# 14_FEP.net
KiCad netlist of a schematic drawn in Altium Designer
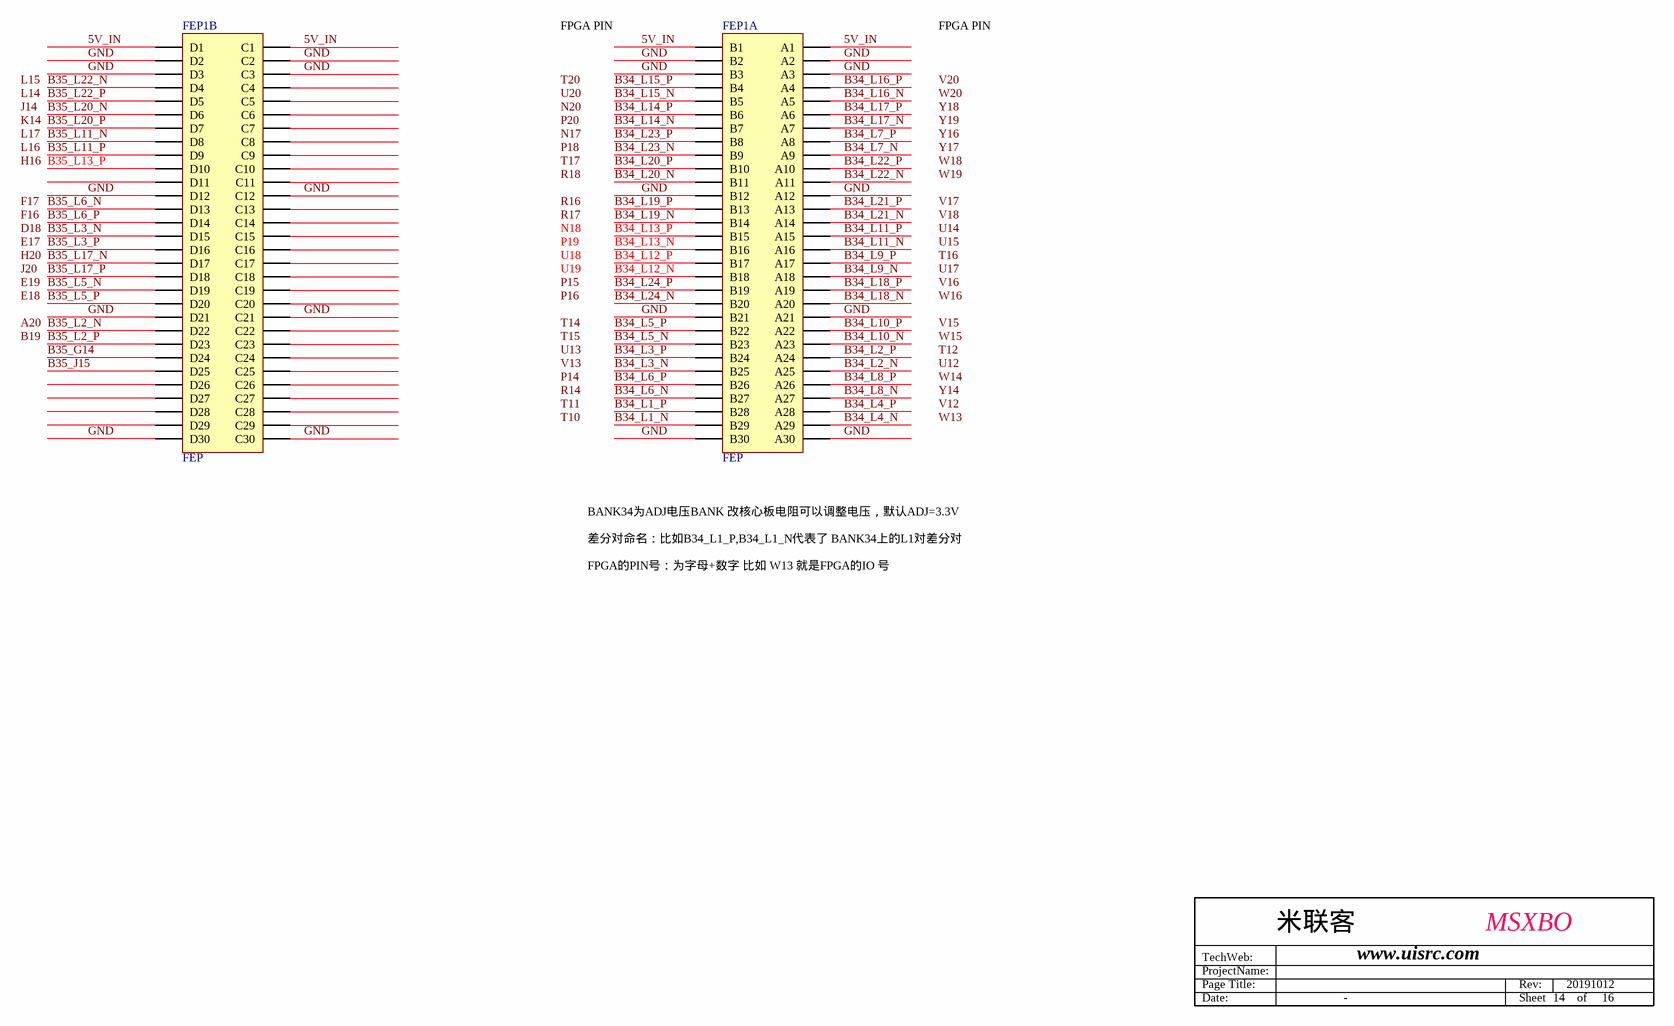
[diagram p0: 14_FEP.SchDoc]

(export (version "E")
  (design (tool "Eeschema 10.0.6"))
  (components
    (comp (ref "FEP1") (value "FEP") (footprint "FEP-X2") (libsource (lib "MIZ7035_Fun") (part "FEP-2X")))
  )
  (nets
    (net (code "1") (name "/5V_IN") (class "Default")
      (node (ref "FEP1") (pin "A1") (pinfunction "A1_A1") (pintype "passive"))
      (node (ref "FEP1") (pin "B1") (pinfunction "B1_B1") (pintype "passive"))
      (node (ref "FEP1") (pin "C1") (pinfunction "C1_C1") (pintype "passive"))
      (node (ref "FEP1") (pin "D1") (pinfunction "D1_D1") (pintype "passive"))
    )
    (net (code "4") (name "/B34_L1_N") (class "Default")
      (node (ref "FEP1") (pin "B29") (pinfunction "B29_B29") (pintype "passive"))
    )
    (net (code "5") (name "/B34_L1_P") (class "Default")
      (node (ref "FEP1") (pin "B28") (pinfunction "B28_B28") (pintype "passive"))
    )
    (net (code "6") (name "/B34_L2_N") (class "Default")
      (node (ref "FEP1") (pin "A25") (pinfunction "A25_A25") (pintype "passive"))
    )
    (net (code "7") (name "/B34_L2_P") (class "Default")
      (node (ref "FEP1") (pin "A24") (pinfunction "A24_A24") (pintype "passive"))
    )
    (net (code "8") (name "/B34_L3_N") (class "Default")
      (node (ref "FEP1") (pin "B25") (pinfunction "B25_B25") (pintype "passive"))
    )
    (net (code "9") (name "/B34_L3_P") (class "Default")
      (node (ref "FEP1") (pin "B24") (pinfunction "B24_B24") (pintype "passive"))
    )
    (net (code "10") (name "/B34_L4_N") (class "Default")
      (node (ref "FEP1") (pin "A29") (pinfunction "A29_A29") (pintype "passive"))
    )
    (net (code "11") (name "/B34_L4_P") (class "Default")
      (node (ref "FEP1") (pin "A28") (pinfunction "A28_A28") (pintype "passive"))
    )
    (net (code "12") (name "/B34_L5_N") (class "Default")
      (node (ref "FEP1") (pin "B23") (pinfunction "B23_B23") (pintype "passive"))
    )
    (net (code "13") (name "/B34_L5_P") (class "Default")
      (node (ref "FEP1") (pin "B22") (pinfunction "B22_B22") (pintype "passive"))
    )
    (net (code "14") (name "/B34_L6_N") (class "Default")
      (node (ref "FEP1") (pin "B27") (pinfunction "B27_B27") (pintype "passive"))
    )
    (net (code "15") (name "/B34_L6_P") (class "Default")
      (node (ref "FEP1") (pin "B26") (pinfunction "B26_B26") (pintype "passive"))
    )
    (net (code "16") (name "/B34_L7_N") (class "Default")
      (node (ref "FEP1") (pin "A9") (pinfunction "A9_A9") (pintype "passive"))
    )
    (net (code "17") (name "/B34_L7_P") (class "Default")
      (node (ref "FEP1") (pin "A8") (pinfunction "A8_A8") (pintype "passive"))
    )
    (net (code "18") (name "/B34_L8_N") (class "Default")
      (node (ref "FEP1") (pin "A27") (pinfunction "A27_A27") (pintype "passive"))
    )
    (net (code "19") (name "/B34_L8_P") (class "Default")
      (node (ref "FEP1") (pin "A26") (pinfunction "A26_A26") (pintype "passive"))
    )
    (net (code "20") (name "/B34_L9_N") (class "Default")
      (node (ref "FEP1") (pin "A18") (pinfunction "A18_A18") (pintype "passive"))
    )
    (net (code "21") (name "/B34_L9_P") (class "Default")
      (node (ref "FEP1") (pin "A17") (pinfunction "A17_A17") (pintype "passive"))
    )
    (net (code "22") (name "/B34_L10_N") (class "Default")
      (node (ref "FEP1") (pin "A23") (pinfunction "A23_A23") (pintype "passive"))
    )
    (net (code "23") (name "/B34_L10_P") (class "Default")
      (node (ref "FEP1") (pin "A22") (pinfunction "A22_A22") (pintype "passive"))
    )
    (net (code "24") (name "/B34_L11_N") (class "Default")
      (node (ref "FEP1") (pin "A16") (pinfunction "A16_A16") (pintype "passive"))
    )
    (net (code "25") (name "/B34_L11_P") (class "Default")
      (node (ref "FEP1") (pin "A15") (pinfunction "A15_A15") (pintype "passive"))
    )
    (net (code "26") (name "/B34_L12_N") (class "Default")
      (node (ref "FEP1") (pin "B18") (pinfunction "B18_B18") (pintype "passive"))
    )
    (net (code "27") (name "/B34_L12_P") (class "Default")
      (node (ref "FEP1") (pin "B17") (pinfunction "B17_B17") (pintype "passive"))
    )
    (net (code "28") (name "/B34_L13_N") (class "Default")
      (node (ref "FEP1") (pin "B16") (pinfunction "B16_B16") (pintype "passive"))
    )
    (net (code "29") (name "/B34_L13_P") (class "Default")
      (node (ref "FEP1") (pin "B15") (pinfunction "B15_B15") (pintype "passive"))
    )
    (net (code "30") (name "/B34_L14_N") (class "Default")
      (node (ref "FEP1") (pin "B7") (pinfunction "B7_B7") (pintype "passive"))
    )
    (net (code "31") (name "/B34_L14_P") (class "Default")
      (node (ref "FEP1") (pin "B6") (pinfunction "B6_B6") (pintype "passive"))
    )
    (net (code "32") (name "/B34_L15_N") (class "Default")
      (node (ref "FEP1") (pin "B5") (pinfunction "B5_B5") (pintype "passive"))
    )
    (net (code "33") (name "/B34_L15_P") (class "Default")
      (node (ref "FEP1") (pin "B4") (pinfunction "B4_B4") (pintype "passive"))
    )
    (net (code "34") (name "/B34_L16_N") (class "Default")
      (node (ref "FEP1") (pin "A5") (pinfunction "A5_A5") (pintype "passive"))
    )
    (net (code "35") (name "/B34_L16_P") (class "Default")
      (node (ref "FEP1") (pin "A4") (pinfunction "A4_A4") (pintype "passive"))
    )
    (net (code "36") (name "/B34_L17_N") (class "Default")
      (node (ref "FEP1") (pin "A7") (pinfunction "A7_A7") (pintype "passive"))
    )
    (net (code "37") (name "/B34_L17_P") (class "Default")
      (node (ref "FEP1") (pin "A6") (pinfunction "A6_A6") (pintype "passive"))
    )
    (net (code "38") (name "/B34_L18_N") (class "Default")
      (node (ref "FEP1") (pin "A20") (pinfunction "A20_A20") (pintype "passive"))
    )
    (net (code "39") (name "/B34_L18_P") (class "Default")
      (node (ref "FEP1") (pin "A19") (pinfunction "A19_A19") (pintype "passive"))
    )
    (net (code "40") (name "/B34_L19_N") (class "Default")
      (node (ref "FEP1") (pin "B14") (pinfunction "B14_B14") (pintype "passive"))
    )
    (net (code "41") (name "/B34_L19_P") (class "Default")
      (node (ref "FEP1") (pin "B13") (pinfunction "B13_B13") (pintype "passive"))
    )
    (net (code "42") (name "/B34_L20_N") (class "Default")
      (node (ref "FEP1") (pin "B11") (pinfunction "B11_B11") (pintype "passive"))
    )
    (net (code "43") (name "/B34_L20_P") (class "Default")
      (node (ref "FEP1") (pin "B10") (pinfunction "B10_B10") (pintype "passive"))
    )
    (net (code "44") (name "/B34_L21_N") (class "Default")
      (node (ref "FEP1") (pin "A14") (pinfunction "A14_A14") (pintype "passive"))
    )
    (net (code "45") (name "/B34_L21_P") (class "Default")
      (node (ref "FEP1") (pin "A13") (pinfunction "A13_A13") (pintype "passive"))
    )
    (net (code "46") (name "/B34_L22_N") (class "Default")
      (node (ref "FEP1") (pin "A11") (pinfunction "A11_A11") (pintype "passive"))
    )
    (net (code "47") (name "/B34_L22_P") (class "Default")
      (node (ref "FEP1") (pin "A10") (pinfunction "A10_A10") (pintype "passive"))
    )
    (net (code "48") (name "/B34_L23_N") (class "Default")
      (node (ref "FEP1") (pin "B9") (pinfunction "B9_B9") (pintype "passive"))
    )
    (net (code "49") (name "/B34_L23_P") (class "Default")
      (node (ref "FEP1") (pin "B8") (pinfunction "B8_B8") (pintype "passive"))
    )
    (net (code "50") (name "/B34_L24_N") (class "Default")
      (node (ref "FEP1") (pin "B20") (pinfunction "B20_B20") (pintype "passive"))
    )
    (net (code "51") (name "/B34_L24_P") (class "Default")
      (node (ref "FEP1") (pin "B19") (pinfunction "B19_B19") (pintype "passive"))
    )
    (net (code "52") (name "/B35_G14") (class "Default")
      (node (ref "FEP1") (pin "D24") (pinfunction "D24_D24") (pintype "passive"))
    )
    (net (code "53") (name "/B35_J15") (class "Default")
      (node (ref "FEP1") (pin "D25") (pinfunction "D25_D25") (pintype "passive"))
    )
    (net (code "54") (name "/B35_L2_N") (class "Default")
      (node (ref "FEP1") (pin "D22") (pinfunction "D22_D22") (pintype "passive"))
    )
    (net (code "55") (name "/B35_L2_P") (class "Default")
      (node (ref "FEP1") (pin "D23") (pinfunction "D23_D23") (pintype "passive"))
    )
    (net (code "56") (name "/B35_L3_N") (class "Default")
      (node (ref "FEP1") (pin "D15") (pinfunction "D15_D15") (pintype "passive"))
    )
    (net (code "57") (name "/B35_L3_P") (class "Default")
      (node (ref "FEP1") (pin "D16") (pinfunction "D16_D16") (pintype "passive"))
    )
    (net (code "58") (name "/B35_L5_N") (class "Default")
      (node (ref "FEP1") (pin "D19") (pinfunction "D19_D19") (pintype "passive"))
    )
    (net (code "59") (name "/B35_L5_P") (class "Default")
      (node (ref "FEP1") (pin "D20") (pinfunction "D20_D20") (pintype "passive"))
    )
    (net (code "60") (name "/B35_L6_N") (class "Default")
      (node (ref "FEP1") (pin "D13") (pinfunction "D13_D13") (pintype "passive"))
    )
    (net (code "61") (name "/B35_L6_P") (class "Default")
      (node (ref "FEP1") (pin "D14") (pinfunction "D14_D14") (pintype "passive"))
    )
    (net (code "62") (name "/B35_L11_N") (class "Default")
      (node (ref "FEP1") (pin "D8") (pinfunction "D8_D8") (pintype "passive"))
    )
    (net (code "63") (name "/B35_L11_P") (class "Default")
      (node (ref "FEP1") (pin "D9") (pinfunction "D9_D9") (pintype "passive"))
    )
    (net (code "64") (name "/B35_L13_P") (class "Default")
      (node (ref "FEP1") (pin "D10") (pinfunction "D10_D10") (pintype "passive"))
    )
    (net (code "65") (name "/B35_L17_N") (class "Default")
      (node (ref "FEP1") (pin "D17") (pinfunction "D17_D17") (pintype "passive"))
    )
    (net (code "66") (name "/B35_L17_P") (class "Default")
      (node (ref "FEP1") (pin "D18") (pinfunction "D18_D18") (pintype "passive"))
    )
    (net (code "67") (name "/B35_L20_N") (class "Default")
      (node (ref "FEP1") (pin "D6") (pinfunction "D6_D6") (pintype "passive"))
    )
    (net (code "68") (name "/B35_L20_P") (class "Default")
      (node (ref "FEP1") (pin "D7") (pinfunction "D7_D7") (pintype "passive"))
    )
    (net (code "69") (name "/B35_L22_N") (class "Default")
      (node (ref "FEP1") (pin "D4") (pinfunction "D4_D4") (pintype "passive"))
    )
    (net (code "70") (name "/B35_L22_P") (class "Default")
      (node (ref "FEP1") (pin "D5") (pinfunction "D5_D5") (pintype "passive"))
    )
    (net (code "77") (name "/GND") (class "Default")
      (node (ref "FEP1") (pin "A12") (pinfunction "A12_A12") (pintype "passive"))
      (node (ref "FEP1") (pin "A2") (pinfunction "A2_A2") (pintype "passive"))
      (node (ref "FEP1") (pin "A21") (pinfunction "A21_A21") (pintype "passive"))
      (node (ref "FEP1") (pin "A3") (pinfunction "A3_A3") (pintype "passive"))
      (node (ref "FEP1") (pin "A30") (pinfunction "A30_A30") (pintype "passive"))
      (node (ref "FEP1") (pin "B12") (pinfunction "B12_B12") (pintype "passive"))
      (node (ref "FEP1") (pin "B2") (pinfunction "B2_B2") (pintype "passive"))
      (node (ref "FEP1") (pin "B21") (pinfunction "B21_B21") (pintype "passive"))
      (node (ref "FEP1") (pin "B3") (pinfunction "B3_B3") (pintype "passive"))
      (node (ref "FEP1") (pin "B30") (pinfunction "B30_B30") (pintype "passive"))
      (node (ref "FEP1") (pin "C12") (pinfunction "C12_C12") (pintype "passive"))
      (node (ref "FEP1") (pin "C2") (pinfunction "C2_C2") (pintype "passive"))
      (node (ref "FEP1") (pin "C21") (pinfunction "C21_C21") (pintype "passive"))
      (node (ref "FEP1") (pin "C3") (pinfunction "C3_C3") (pintype "passive"))
      (node (ref "FEP1") (pin "C30") (pinfunction "C30_C30") (pintype "passive"))
      (node (ref "FEP1") (pin "D12") (pinfunction "D12_D12") (pintype "passive"))
      (node (ref "FEP1") (pin "D2") (pinfunction "D2_D2") (pintype "passive"))
      (node (ref "FEP1") (pin "D21") (pinfunction "D21_D21") (pintype "passive"))
      (node (ref "FEP1") (pin "D3") (pinfunction "D3_D3") (pintype "passive"))
      (node (ref "FEP1") (pin "D30") (pinfunction "D30_D30") (pintype "passive"))
    )
    (net (code "135") (name "unconnected-(FEP1-PadC4)") (class "Default")
      (node (ref "FEP1") (pin "C4") (pinfunction "C4_C4") (pintype "passive"))
    )
    (net (code "136") (name "unconnected-(FEP1-PadC5)") (class "Default")
      (node (ref "FEP1") (pin "C5") (pinfunction "C5_C5") (pintype "passive"))
    )
    (net (code "137") (name "unconnected-(FEP1-PadC6)") (class "Default")
      (node (ref "FEP1") (pin "C6") (pinfunction "C6_C6") (pintype "passive"))
    )
    (net (code "138") (name "unconnected-(FEP1-PadC7)") (class "Default")
      (node (ref "FEP1") (pin "C7") (pinfunction "C7_C7") (pintype "passive"))
    )
    (net (code "139") (name "unconnected-(FEP1-PadC8)") (class "Default")
      (node (ref "FEP1") (pin "C8") (pinfunction "C8_C8") (pintype "passive"))
    )
    (net (code "140") (name "unconnected-(FEP1-PadC9)") (class "Default")
      (node (ref "FEP1") (pin "C9") (pinfunction "C9_C9") (pintype "passive"))
    )
    (net (code "141") (name "unconnected-(FEP1-PadC10)") (class "Default")
      (node (ref "FEP1") (pin "C10") (pinfunction "C10_C10") (pintype "passive"))
    )
    (net (code "142") (name "unconnected-(FEP1-PadC11)") (class "Default")
      (node (ref "FEP1") (pin "C11") (pinfunction "C11_C11") (pintype "passive"))
    )
    (net (code "143") (name "unconnected-(FEP1-PadC13)") (class "Default")
      (node (ref "FEP1") (pin "C13") (pinfunction "C13_C13") (pintype "passive"))
    )
    (net (code "144") (name "unconnected-(FEP1-PadC14)") (class "Default")
      (node (ref "FEP1") (pin "C14") (pinfunction "C14_C14") (pintype "passive"))
    )
    (net (code "145") (name "unconnected-(FEP1-PadC15)") (class "Default")
      (node (ref "FEP1") (pin "C15") (pinfunction "C15_C15") (pintype "passive"))
    )
    (net (code "146") (name "unconnected-(FEP1-PadC16)") (class "Default")
      (node (ref "FEP1") (pin "C16") (pinfunction "C16_C16") (pintype "passive"))
    )
    (net (code "147") (name "unconnected-(FEP1-PadC17)") (class "Default")
      (node (ref "FEP1") (pin "C17") (pinfunction "C17_C17") (pintype "passive"))
    )
    (net (code "148") (name "unconnected-(FEP1-PadC18)") (class "Default")
      (node (ref "FEP1") (pin "C18") (pinfunction "C18_C18") (pintype "passive"))
    )
    (net (code "149") (name "unconnected-(FEP1-PadC19)") (class "Default")
      (node (ref "FEP1") (pin "C19") (pinfunction "C19_C19") (pintype "passive"))
    )
    (net (code "150") (name "unconnected-(FEP1-PadC20)") (class "Default")
      (node (ref "FEP1") (pin "C20") (pinfunction "C20_C20") (pintype "passive"))
    )
    (net (code "151") (name "unconnected-(FEP1-PadC22)") (class "Default")
      (node (ref "FEP1") (pin "C22") (pinfunction "C22_C22") (pintype "passive"))
    )
    (net (code "152") (name "unconnected-(FEP1-PadC23)") (class "Default")
      (node (ref "FEP1") (pin "C23") (pinfunction "C23_C23") (pintype "passive"))
    )
    (net (code "153") (name "unconnected-(FEP1-PadC24)") (class "Default")
      (node (ref "FEP1") (pin "C24") (pinfunction "C24_C24") (pintype "passive"))
    )
    (net (code "154") (name "unconnected-(FEP1-PadC25)") (class "Default")
      (node (ref "FEP1") (pin "C25") (pinfunction "C25_C25") (pintype "passive"))
    )
    (net (code "155") (name "unconnected-(FEP1-PadC26)") (class "Default")
      (node (ref "FEP1") (pin "C26") (pinfunction "C26_C26") (pintype "passive"))
    )
    (net (code "156") (name "unconnected-(FEP1-PadC27)") (class "Default")
      (node (ref "FEP1") (pin "C27") (pinfunction "C27_C27") (pintype "passive"))
    )
    (net (code "157") (name "unconnected-(FEP1-PadC28)") (class "Default")
      (node (ref "FEP1") (pin "C28") (pinfunction "C28_C28") (pintype "passive"))
    )
    (net (code "158") (name "unconnected-(FEP1-PadC29)") (class "Default")
      (node (ref "FEP1") (pin "C29") (pinfunction "C29_C29") (pintype "passive"))
    )
    (net (code "159") (name "unconnected-(FEP1-PadD11)") (class "Default")
      (node (ref "FEP1") (pin "D11") (pinfunction "D11_D11") (pintype "passive"))
    )
    (net (code "160") (name "unconnected-(FEP1-PadD26)") (class "Default")
      (node (ref "FEP1") (pin "D26") (pinfunction "D26_D26") (pintype "passive"))
    )
    (net (code "161") (name "unconnected-(FEP1-PadD27)") (class "Default")
      (node (ref "FEP1") (pin "D27") (pinfunction "D27_D27") (pintype "passive"))
    )
    (net (code "162") (name "unconnected-(FEP1-PadD28)") (class "Default")
      (node (ref "FEP1") (pin "D28") (pinfunction "D28_D28") (pintype "passive"))
    )
    (net (code "163") (name "unconnected-(FEP1-PadD29)") (class "Default")
      (node (ref "FEP1") (pin "D29") (pinfunction "D29_D29") (pintype "passive"))
    )
  )
)
